# MCU.net
KiCad netlist of a schematic drawn in Altium Designer
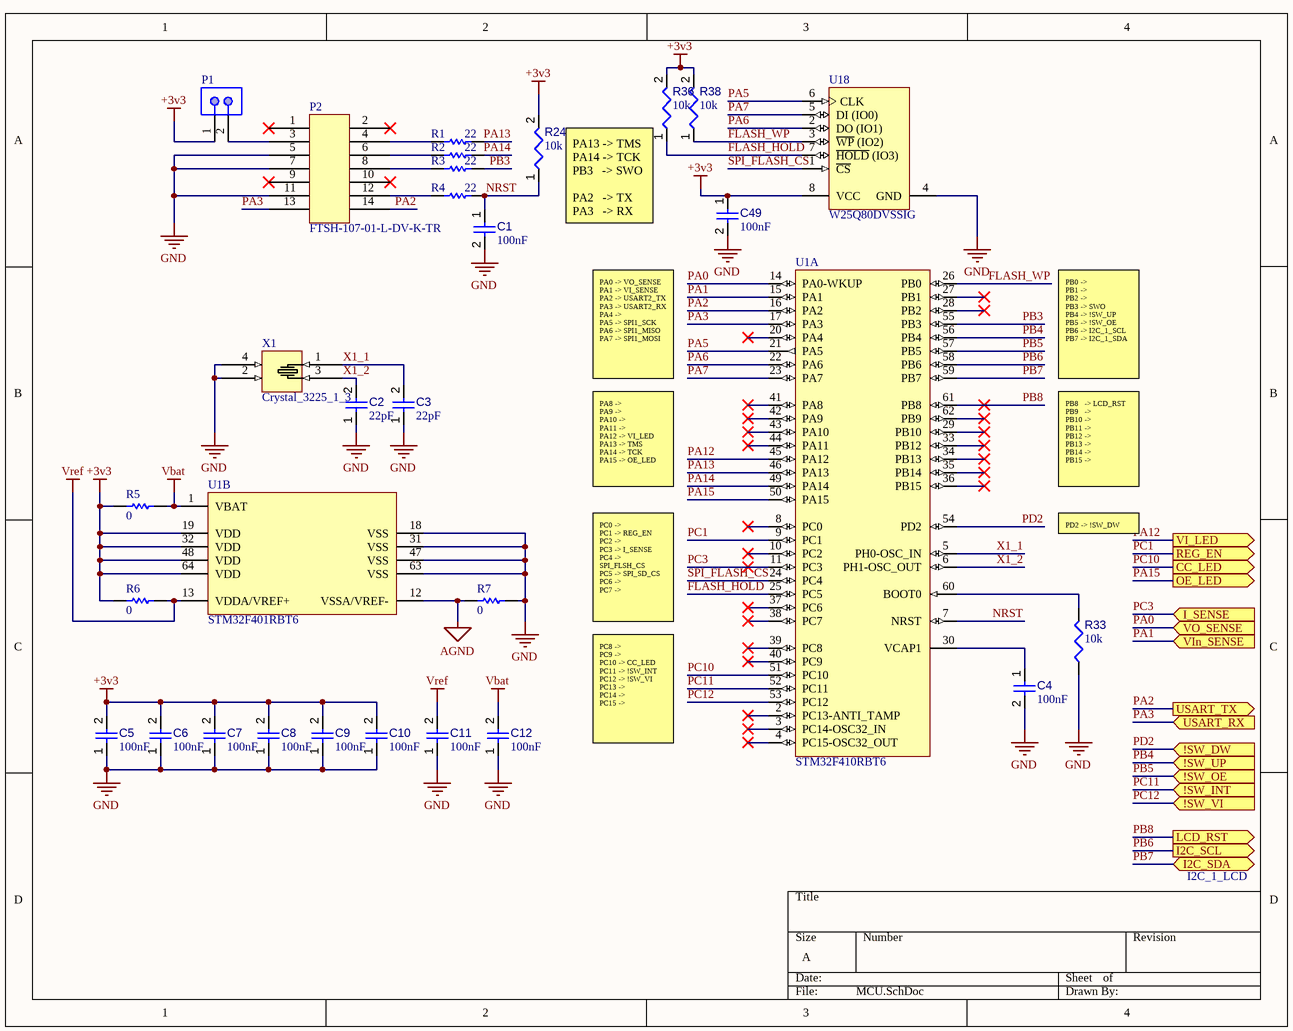
[diagram p0: MCU.SchDoc]

(export (version "E")
  (design (tool "Eeschema 10.0.6"))
  (components
    (comp (ref "C1")
      (value "100nF")
      (footprint "CAPC2013X95X50ML10T25")
      (description "Chip Capacitor, 100 nF, +/- 10%, 50 V, 0805 (2012 Metric)")
      (fields (field (name "TOLERANCE") "10%") (field (name "Comment") "Capacitor 100 nF +/-10% 50 V 0805"))
      (libsource (lib "Aditya Sehgal") (part "CAP-NP-2"))
    )
    (comp (ref "C2")
      (value "22pF")
      (footprint "CAPC2013X95X50ML10T25")
      (description "Chip Capacitor, 100 nF, +/- 10%, 50 V, 0805 (2012 Metric)")
      (fields (field (name "TOLERANCE") "10%") (field (name "Comment") "Capacitor 100 nF +/-10% 50 V 0805"))
      (libsource (lib "Aditya Sehgal") (part "CAP-NP-2"))
    )
    (comp (ref "C3")
      (value "22pF")
      (footprint "CAPC2013X95X50ML10T25")
      (description "Chip Capacitor, 100 nF, +/- 10%, 50 V, 0805 (2012 Metric)")
      (fields (field (name "TOLERANCE") "10%") (field (name "Comment") "Capacitor 100 nF +/-10% 50 V 0805"))
      (libsource (lib "Aditya Sehgal") (part "CAP-NP-2"))
    )
    (comp (ref "C4")
      (value "100nF")
      (footprint "CAPC2013X95X50ML10T25")
      (description "Chip Capacitor, 100 nF, +/- 10%, 50 V, 0805 (2012 Metric)")
      (fields (field (name "TOLERANCE") "10%") (field (name "Comment") "Capacitor 100 nF +/-10% 50 V 0805"))
      (libsource (lib "Aditya Sehgal") (part "CAP-NP-2"))
    )
    (comp (ref "C5")
      (value "100nF")
      (footprint "CAPC2013X95X50ML10T25")
      (description "Chip Capacitor, 100 nF, +/- 10%, 50 V, 0805 (2012 Metric)")
      (fields (field (name "TOLERANCE") "10%") (field (name "Comment") "Capacitor 100 nF +/-10% 50 V 0805"))
      (libsource (lib "Aditya Sehgal") (part "CAP-NP-2"))
    )
    (comp (ref "C6")
      (value "100nF")
      (footprint "CAPC2013X95X50ML10T25")
      (description "Chip Capacitor, 100 nF, +/- 10%, 50 V, 0805 (2012 Metric)")
      (fields (field (name "TOLERANCE") "10%") (field (name "Comment") "Capacitor 100 nF +/-10% 50 V 0805"))
      (libsource (lib "Aditya Sehgal") (part "CAP-NP-2"))
    )
    (comp (ref "C7")
      (value "100nF")
      (footprint "CAPC2013X95X50ML10T25")
      (description "Chip Capacitor, 100 nF, +/- 10%, 50 V, 0805 (2012 Metric)")
      (fields (field (name "TOLERANCE") "10%") (field (name "Comment") "Capacitor 100 nF +/-10% 50 V 0805"))
      (libsource (lib "Aditya Sehgal") (part "CAP-NP-2"))
    )
    (comp (ref "C8")
      (value "100nF")
      (footprint "CAPC2013X95X50ML10T25")
      (description "Chip Capacitor, 100 nF, +/- 10%, 50 V, 0805 (2012 Metric)")
      (fields (field (name "TOLERANCE") "10%") (field (name "Comment") "Capacitor 100 nF +/-10% 50 V 0805"))
      (libsource (lib "Aditya Sehgal") (part "CAP-NP-2"))
    )
    (comp (ref "C9")
      (value "100nF")
      (footprint "CAPC2013X95X50ML10T25")
      (description "Chip Capacitor, 100 nF, +/- 10%, 50 V, 0805 (2012 Metric)")
      (fields (field (name "TOLERANCE") "10%") (field (name "Comment") "Capacitor 100 nF +/-10% 50 V 0805"))
      (libsource (lib "Aditya Sehgal") (part "CAP-NP-2"))
    )
    (comp (ref "C10")
      (value "100nF")
      (footprint "CAPC2013X95X50ML10T25")
      (description "Chip Capacitor, 100 nF, +/- 10%, 50 V, 0805 (2012 Metric)")
      (fields (field (name "TOLERANCE") "10%") (field (name "Comment") "Capacitor 100 nF +/-10% 50 V 0805"))
      (libsource (lib "Aditya Sehgal") (part "CAP-NP-2"))
    )
    (comp (ref "C11")
      (value "100nF")
      (footprint "CAPC2013X95X50ML10T25")
      (description "Chip Capacitor, 100 nF, +/- 10%, 50 V, 0805 (2012 Metric)")
      (fields (field (name "TOLERANCE") "10%") (field (name "Comment") "Capacitor 100 nF +/-10% 50 V 0805"))
      (libsource (lib "Aditya Sehgal") (part "CAP-NP-2"))
    )
    (comp (ref "C12")
      (value "100nF")
      (footprint "CAPC2013X95X50ML10T25")
      (description "Chip Capacitor, 100 nF, +/- 10%, 50 V, 0805 (2012 Metric)")
      (fields (field (name "TOLERANCE") "10%") (field (name "Comment") "Capacitor 100 nF +/-10% 50 V 0805"))
      (libsource (lib "Aditya Sehgal") (part "CAP-NP-2"))
    )
    (comp (ref "C49")
      (value "100nF")
      (footprint "CAPC2013X95X50LL10T25")
      (description "Chip Capacitor, 100 nF, +/- 10%, 50 V, 0805 (2012 Metric)")
      (fields (field (name "TOLERANCE") "10%") (field (name "Comment") "Capacitor 100 nF +/-10% 50 V 0805"))
      (libsource (lib "Knightscope, Inc") (part "CAP-NP-2"))
    )
    (comp (ref "P1")
      (value "GRPB021VWVN-RC")
      (footprint "SLIN-GRPB021VWVN-RC_V")
      (fields (field (name "MANUFACTURER") "Sullins"))
      (libsource (lib "Altium Content Vault") (part "CN-1P-M-R2"))
    )
    (comp (ref "P2")
      (value "FTSH-107-01-L-DV-K-TR")
      (footprint "FTSH-107-01-L-DV-K-TR-Footprint-1")
      (description "Conn Unshrouded Header HDR 14 POS 1.27mm Solder ST SMD T/R")
      (libsource (lib "University of California Santa Cruz") (part "FTSH-107-01-L-DV-K-TR"))
    )
    (comp (ref "R1")
      (value "22")
      (footprint "RESC2013X50X35ML15T15")
      (description "Chip Resistor, 0 Ohm, +/- 1%, 125 mW, -55 to 155 degC, 0805 (2012 Metric)")
      (fields (field (name "TOLERANCE") "1%") (field (name "POWER") "125mW"))
      (libsource (lib "Aditya Sehgal") (part "RES-2"))
    )
    (comp (ref "R2")
      (value "22")
      (footprint "RESC2013X50X35ML15T15")
      (description "Chip Resistor, 0 Ohm, +/- 1%, 125 mW, -55 to 155 degC, 0805 (2012 Metric)")
      (fields (field (name "TOLERANCE") "1%") (field (name "POWER") "125mW"))
      (libsource (lib "Aditya Sehgal") (part "RES-2"))
    )
    (comp (ref "R3")
      (value "22")
      (footprint "RESC2013X50X35ML15T15")
      (description "Chip Resistor, 0 Ohm, +/- 1%, 125 mW, -55 to 155 degC, 0805 (2012 Metric)")
      (fields (field (name "TOLERANCE") "1%") (field (name "POWER") "125mW"))
      (libsource (lib "Aditya Sehgal") (part "RES-2"))
    )
    (comp (ref "R4")
      (value "22")
      (footprint "RESC2013X50X35ML15T15")
      (description "Chip Resistor, 0 Ohm, +/- 1%, 125 mW, -55 to 155 degC, 0805 (2012 Metric)")
      (fields (field (name "TOLERANCE") "1%") (field (name "POWER") "125mW"))
      (libsource (lib "Aditya Sehgal") (part "RES-2"))
    )
    (comp (ref "R5")
      (value "0")
      (footprint "RESC2013X50X35ML15T15")
      (description "Chip Resistor, 0 Ohm, +/- 1%, 125 mW, -55 to 155 degC, 0805 (2012 Metric)")
      (fields (field (name "TOLERANCE") "1%") (field (name "POWER") "125mW"))
      (libsource (lib "Aditya Sehgal") (part "RES-2"))
    )
    (comp (ref "R6")
      (value "0")
      (footprint "RESC2013X50X35ML15T15")
      (description "Chip Resistor, 0 Ohm, +/- 1%, 125 mW, -55 to 155 degC, 0805 (2012 Metric)")
      (fields (field (name "TOLERANCE") "1%") (field (name "POWER") "125mW"))
      (libsource (lib "Aditya Sehgal") (part "RES-2"))
    )
    (comp (ref "R7")
      (value "0")
      (footprint "RESC2013X50X35ML15T15")
      (description "Chip Resistor, 0 Ohm, +/- 1%, 125 mW, -55 to 155 degC, 0805 (2012 Metric)")
      (fields (field (name "TOLERANCE") "1%") (field (name "POWER") "125mW"))
      (libsource (lib "Aditya Sehgal") (part "RES-2"))
    )
    (comp (ref "R24")
      (value "10k")
      (footprint "RESC2013X50X35ML15T15")
      (description "Chip Resistor, 10 KOhm, +/- 1%, 125 mW, -55 to 155 degC, 0805 (2012 Metric)")
      (fields (field (name "TOLERANCE") "1%") (field (name "POWER") "125mW"))
      (libsource (lib "Knightscope, Inc") (part "RES-2"))
    )
    (comp (ref "R33")
      (value "10k")
      (footprint "RESC0805(2012)_L")
      (description "Chip Resistor, 470 Ohms, +/-5%, 125 mW, -55 to 155 degC, 0805")
      (fields (field (name "POWER") "125mW") (field (name "TOLERANCE") "5%"))
      (libsource (lib "University of California Santa Cruz") (part "RES-2"))
    )
    (comp (ref "R36")
      (value "10k")
      (footprint "RESC2013X50X35ML15T15")
      (description "Chip Resistor, 10 KOhm, +/- 1%, 125 mW, -55 to 155 degC, 0805 (2012 Metric)")
      (fields (field (name "TOLERANCE") "1%") (field (name "POWER") "125mW"))
      (libsource (lib "Knightscope, Inc") (part "RES-2"))
    )
    (comp (ref "R38")
      (value "10k")
      (footprint "RESC2013X50X35ML15T15")
      (description "Chip Resistor, 10 KOhm, +/- 1%, 125 mW, -55 to 155 degC, 0805 (2012 Metric)")
      (fields (field (name "TOLERANCE") "1%") (field (name "POWER") "125mW"))
      (libsource (lib "Knightscope, Inc") (part "RES-2"))
    )
    (comp (ref "U1")
      (value "STM32F410RBT6")
      (footprint "STM-LQFP64_N")
      (fields (field (name "MANUFACTURER") "STMicroelectronics") (field (name "PARTNUMBER") "STM32F401RBT6"))
      (libsource (lib "Altium Content Vault") (part "MC-ARM-STM32F401-SQ64"))
    )
    (comp (ref "U18")
      (value "W25Q80DVSSIG")
      (footprint "WINB-SOIC-8_L")
      (fields (field (name "MANUFACTURER") "WinbondElectronics"))
      (libsource (lib "Altium Content Vault") (part "WINB-W25Q80DV-8"))
    )
    (comp (ref "X1")
      (value "Crystal_3225_1_3")
      (footprint "Crystal_3225_1_3-Footprint-1")
      (description "3225 crystal")
      (libsource (lib "Aditya Sehgal") (part "Crystal_4pin_1_3"))
    )
  )
  (nets
    (net (code "1") (name "+3v3") (class "Default")
      (node (ref "C10") (pin "2") (pinfunction "2_2") (pintype "passive"))
      (node (ref "C49") (pin "1") (pinfunction "1_1") (pintype "passive"))
      (node (ref "C5") (pin "2") (pinfunction "2_2") (pintype "passive"))
      (node (ref "C6") (pin "2") (pinfunction "2_2") (pintype "passive"))
      (node (ref "C7") (pin "2") (pinfunction "2_2") (pintype "passive"))
      (node (ref "C8") (pin "2") (pinfunction "2_2") (pintype "passive"))
      (node (ref "C9") (pin "2") (pinfunction "2_2") (pintype "passive"))
      (node (ref "P1") (pin "1") (pinfunction "1_1") (pintype "passive"))
      (node (ref "R24") (pin "2") (pinfunction "2_2") (pintype "passive"))
      (node (ref "R36") (pin "2") (pinfunction "2_2") (pintype "passive"))
      (node (ref "R38") (pin "2") (pinfunction "2_2") (pintype "passive"))
      (node (ref "R5") (pin "1") (pinfunction "1_1") (pintype "passive"))
      (node (ref "R6") (pin "1") (pinfunction "1_1") (pintype "passive"))
      (node (ref "U1") (pin "19") (pinfunction "VDD_19") (pintype "power_in"))
      (node (ref "U1") (pin "32") (pinfunction "VDD_32") (pintype "power_in"))
      (node (ref "U1") (pin "48") (pinfunction "VDD_48") (pintype "power_in"))
      (node (ref "U1") (pin "64") (pinfunction "VDD_64") (pintype "power_in"))
      (node (ref "U18") (pin "8") (pinfunction "VCC_8") (pintype "power_in"))
    )
    (net (code "2") (name "/FLASH_HOLD") (class "Default")
      (node (ref "R36") (pin "1") (pinfunction "1_1") (pintype "passive"))
      (node (ref "U1") (pin "25") (pinfunction "PC5_25") (pintype "bidirectional"))
      (node (ref "U18") (pin "7") (pinfunction "~{HOLD}_(IO3)_7") (pintype "bidirectional"))
    )
    (net (code "3") (name "/FLASH_WP") (class "Default")
      (node (ref "R38") (pin "1") (pinfunction "1_1") (pintype "passive"))
      (node (ref "U1") (pin "26") (pinfunction "PB0_26") (pintype "bidirectional"))
      (node (ref "U18") (pin "3") (pinfunction "~{WP}_(IO2)_3") (pintype "bidirectional"))
    )
    (net (code "4") (name "/NRST") (class "Default")
      (node (ref "C1") (pin "1") (pinfunction "1_1") (pintype "passive"))
      (node (ref "R24") (pin "1") (pinfunction "1_1") (pintype "passive"))
      (node (ref "R4") (pin "2") (pinfunction "2_2") (pintype "passive"))
      (node (ref "U1") (pin "7") (pinfunction "NRST_7") (pintype "bidirectional"))
    )
    (net (code "5") (name "/PA0") (class "Default")
      (node (ref "U1") (pin "14") (pinfunction "PA0-WKUP_14") (pintype "bidirectional"))
    )
    (net (code "6") (name "/PA1") (class "Default")
      (node (ref "U1") (pin "15") (pinfunction "PA1_15") (pintype "bidirectional"))
    )
    (net (code "7") (name "/PA2") (class "Default")
      (node (ref "P2") (pin "14") (pinfunction "14_14") (pintype "passive"))
      (node (ref "U1") (pin "16") (pinfunction "PA2_16") (pintype "bidirectional"))
    )
    (net (code "8") (name "/PA3") (class "Default")
      (node (ref "P2") (pin "13") (pinfunction "13_13") (pintype "passive"))
      (node (ref "U1") (pin "17") (pinfunction "PA3_17") (pintype "bidirectional"))
    )
    (net (code "9") (name "/PA5") (class "Default")
      (node (ref "U1") (pin "21") (pinfunction "PA5_21") (pintype "bidirectional"))
      (node (ref "U18") (pin "6") (pinfunction "CLK_6") (pintype "input"))
    )
    (net (code "10") (name "/PA6") (class "Default")
      (node (ref "U1") (pin "22") (pinfunction "PA6_22") (pintype "bidirectional"))
      (node (ref "U18") (pin "2") (pinfunction "DO_(IO1)_2") (pintype "bidirectional"))
    )
    (net (code "11") (name "/PA7") (class "Default")
      (node (ref "U1") (pin "23") (pinfunction "PA7_23") (pintype "bidirectional"))
      (node (ref "U18") (pin "5") (pinfunction "DI_(IO0)_5") (pintype "bidirectional"))
    )
    (net (code "12") (name "/PA12") (class "Default")
      (node (ref "U1") (pin "45") (pinfunction "PA12_45") (pintype "bidirectional"))
    )
    (net (code "13") (name "/PA13") (class "Default")
      (node (ref "R1") (pin "2") (pinfunction "2_2") (pintype "passive"))
      (node (ref "U1") (pin "46") (pinfunction "PA13_46") (pintype "bidirectional"))
    )
    (net (code "14") (name "/PA14") (class "Default")
      (node (ref "R2") (pin "2") (pinfunction "2_2") (pintype "passive"))
      (node (ref "U1") (pin "49") (pinfunction "PA14_49") (pintype "bidirectional"))
    )
    (net (code "15") (name "/PA15") (class "Default")
      (node (ref "U1") (pin "50") (pinfunction "PA15_50") (pintype "bidirectional"))
    )
    (net (code "16") (name "/PB3") (class "Default")
      (node (ref "R3") (pin "2") (pinfunction "2_2") (pintype "passive"))
      (node (ref "U1") (pin "55") (pinfunction "PB3_55") (pintype "bidirectional"))
    )
    (net (code "17") (name "/PB4") (class "Default")
      (node (ref "U1") (pin "56") (pinfunction "PB4_56") (pintype "bidirectional"))
    )
    (net (code "18") (name "/PB5") (class "Default")
      (node (ref "U1") (pin "57") (pinfunction "PB5_57") (pintype "bidirectional"))
    )
    (net (code "19") (name "/PB6") (class "Default")
      (node (ref "U1") (pin "58") (pinfunction "PB6_58") (pintype "bidirectional"))
    )
    (net (code "20") (name "/PB7") (class "Default")
      (node (ref "U1") (pin "59") (pinfunction "PB7_59") (pintype "bidirectional"))
    )
    (net (code "21") (name "/PB8") (class "Default")
      (node (ref "U1") (pin "61") (pinfunction "PB8_61") (pintype "bidirectional"))
    )
    (net (code "22") (name "/PC1") (class "Default")
      (node (ref "U1") (pin "9") (pinfunction "PC1_9") (pintype "bidirectional"))
    )
    (net (code "23") (name "/PC3") (class "Default")
      (node (ref "U1") (pin "11") (pinfunction "PC3_11") (pintype "bidirectional"))
    )
    (net (code "24") (name "/PC10") (class "Default")
      (node (ref "U1") (pin "51") (pinfunction "PC10_51") (pintype "bidirectional"))
    )
    (net (code "25") (name "/PC11") (class "Default")
      (node (ref "U1") (pin "52") (pinfunction "PC11_52") (pintype "bidirectional"))
    )
    (net (code "26") (name "/PC12") (class "Default")
      (node (ref "U1") (pin "53") (pinfunction "PC12_53") (pintype "bidirectional"))
    )
    (net (code "27") (name "/PD2") (class "Default")
      (node (ref "U1") (pin "54") (pinfunction "PD2_54") (pintype "bidirectional"))
    )
    (net (code "28") (name "/SPI_FLASH_CS") (class "Default")
      (node (ref "U1") (pin "24") (pinfunction "PC4_24") (pintype "bidirectional"))
      (node (ref "U18") (pin "1") (pinfunction "~{CS}_1") (pintype "input"))
    )
    (net (code "29") (name "/X1_1") (class "Default")
      (node (ref "C3") (pin "2") (pinfunction "2_2") (pintype "passive"))
      (node (ref "U1") (pin "5") (pinfunction "PH0-OSC_IN_5") (pintype "bidirectional"))
      (node (ref "X1") (pin "1") (pinfunction "X1_1") (pintype "input"))
    )
    (net (code "30") (name "/X1_2") (class "Default")
      (node (ref "C2") (pin "2") (pinfunction "2_2") (pintype "passive"))
      (node (ref "U1") (pin "6") (pinfunction "PH1-OSC_OUT_6") (pintype "bidirectional"))
      (node (ref "X1") (pin "3") (pinfunction "X2_3") (pintype "input"))
    )
    (net (code "31") (name "AGND") (class "Default")
      (node (ref "R7") (pin "1") (pinfunction "1_1") (pintype "passive"))
      (node (ref "U1") (pin "12") (pinfunction "VSSA/VREF-_12") (pintype "power_in"))
    )
    (net (code "32") (name "GND") (class "Default")
      (node (ref "C1") (pin "2") (pinfunction "2_2") (pintype "passive"))
      (node (ref "C10") (pin "1") (pinfunction "1_1") (pintype "passive"))
      (node (ref "C11") (pin "1") (pinfunction "1_1") (pintype "passive"))
      (node (ref "C12") (pin "1") (pinfunction "1_1") (pintype "passive"))
      (node (ref "C2") (pin "1") (pinfunction "1_1") (pintype "passive"))
      (node (ref "C3") (pin "1") (pinfunction "1_1") (pintype "passive"))
      (node (ref "C4") (pin "2") (pinfunction "2_2") (pintype "passive"))
      (node (ref "C49") (pin "2") (pinfunction "2_2") (pintype "passive"))
      (node (ref "C5") (pin "1") (pinfunction "1_1") (pintype "passive"))
      (node (ref "C6") (pin "1") (pinfunction "1_1") (pintype "passive"))
      (node (ref "C7") (pin "1") (pinfunction "1_1") (pintype "passive"))
      (node (ref "C8") (pin "1") (pinfunction "1_1") (pintype "passive"))
      (node (ref "C9") (pin "1") (pinfunction "1_1") (pintype "passive"))
      (node (ref "P2") (pin "11") (pinfunction "11_11") (pintype "passive"))
      (node (ref "P2") (pin "5") (pinfunction "5_5") (pintype "passive"))
      (node (ref "P2") (pin "7") (pinfunction "7_7") (pintype "passive"))
      (node (ref "R33") (pin "1") (pinfunction "1_1") (pintype "passive"))
      (node (ref "R7") (pin "2") (pinfunction "2_2") (pintype "passive"))
      (node (ref "U1") (pin "18") (pinfunction "VSS_18") (pintype "power_in"))
      (node (ref "U1") (pin "31") (pinfunction "VSS_31") (pintype "power_in"))
      (node (ref "U1") (pin "47") (pinfunction "VSS_47") (pintype "power_in"))
      (node (ref "U1") (pin "63") (pinfunction "VSS_63") (pintype "power_in"))
      (node (ref "U18") (pin "4") (pinfunction "GND_4") (pintype "power_in"))
      (node (ref "X1") (pin "2") (pinfunction "GND_2") (pintype "input"))
      (node (ref "X1") (pin "4") (pinfunction "GND_4") (pintype "input"))
    )
    (net (code "33") (name "Net-(P1-Pad2)") (class "Default")
      (node (ref "P1") (pin "2") (pinfunction "2_2") (pintype "passive"))
      (node (ref "P2") (pin "3") (pinfunction "3_3") (pintype "passive"))
    )
    (net (code "34") (name "Net-(P2-Pad4)") (class "Default")
      (node (ref "P2") (pin "4") (pinfunction "4_4") (pintype "passive"))
      (node (ref "R1") (pin "1") (pinfunction "1_1") (pintype "passive"))
    )
    (net (code "35") (name "Net-(P2-Pad6)") (class "Default")
      (node (ref "P2") (pin "6") (pinfunction "6_6") (pintype "passive"))
      (node (ref "R2") (pin "1") (pinfunction "1_1") (pintype "passive"))
    )
    (net (code "36") (name "Net-(P2-Pad8)") (class "Default")
      (node (ref "P2") (pin "8") (pinfunction "8_8") (pintype "passive"))
      (node (ref "R3") (pin "1") (pinfunction "1_1") (pintype "passive"))
    )
    (net (code "37") (name "Net-(P2-Pad12)") (class "Default")
      (node (ref "P2") (pin "12") (pinfunction "12_12") (pintype "passive"))
      (node (ref "R4") (pin "1") (pinfunction "1_1") (pintype "passive"))
    )
    (net (code "38") (name "Net-(U1A-BOOT0)") (class "Default")
      (node (ref "R33") (pin "2") (pinfunction "2_2") (pintype "passive"))
      (node (ref "U1") (pin "60") (pinfunction "BOOT0_60") (pintype "input"))
    )
    (net (code "39") (name "Net-(U1A-VCAP1)") (class "Default")
      (node (ref "C4") (pin "1") (pinfunction "1_1") (pintype "passive"))
      (node (ref "U1") (pin "30") (pinfunction "VCAP1_30") (pintype "power_in"))
    )
    (net (code "40") (name "Vbat") (class "Default")
      (node (ref "C12") (pin "2") (pinfunction "2_2") (pintype "passive"))
      (node (ref "R5") (pin "2") (pinfunction "2_2") (pintype "passive"))
      (node (ref "U1") (pin "1") (pinfunction "VBAT_1") (pintype "power_in"))
    )
    (net (code "41") (name "Vref") (class "Default")
      (node (ref "C11") (pin "2") (pinfunction "2_2") (pintype "passive"))
      (node (ref "R6") (pin "2") (pinfunction "2_2") (pintype "passive"))
      (node (ref "U1") (pin "13") (pinfunction "VDDA/VREF+_13") (pintype "power_in"))
    )
    (net (code "42") (name "unconnected-(P2-Pad1)") (class "Default")
      (node (ref "P2") (pin "1") (pinfunction "1_1") (pintype "passive+no_connect"))
    )
    (net (code "43") (name "unconnected-(P2-Pad2)") (class "Default")
      (node (ref "P2") (pin "2") (pinfunction "2_2") (pintype "passive+no_connect"))
    )
    (net (code "44") (name "unconnected-(P2-Pad9)") (class "Default")
      (node (ref "P2") (pin "9") (pinfunction "9_9") (pintype "passive+no_connect"))
    )
    (net (code "45") (name "unconnected-(P2-Pad10)") (class "Default")
      (node (ref "P2") (pin "10") (pinfunction "10_10") (pintype "passive+no_connect"))
    )
    (net (code "46") (name "unconnected-(U1A-PA4-Pad20)") (class "Default")
      (node (ref "U1") (pin "20") (pinfunction "PA4_20") (pintype "bidirectional+no_connect"))
    )
    (net (code "47") (name "unconnected-(U1A-PA8-Pad41)") (class "Default")
      (node (ref "U1") (pin "41") (pinfunction "PA8_41") (pintype "bidirectional+no_connect"))
    )
    (net (code "48") (name "unconnected-(U1A-PA9-Pad42)") (class "Default")
      (node (ref "U1") (pin "42") (pinfunction "PA9_42") (pintype "bidirectional+no_connect"))
    )
    (net (code "49") (name "unconnected-(U1A-PA10-Pad43)") (class "Default")
      (node (ref "U1") (pin "43") (pinfunction "PA10_43") (pintype "bidirectional+no_connect"))
    )
    (net (code "50") (name "unconnected-(U1A-PA11-Pad44)") (class "Default")
      (node (ref "U1") (pin "44") (pinfunction "PA11_44") (pintype "bidirectional+no_connect"))
    )
    (net (code "51") (name "unconnected-(U1A-PB1-Pad27)") (class "Default")
      (node (ref "U1") (pin "27") (pinfunction "PB1_27") (pintype "bidirectional+no_connect"))
    )
    (net (code "52") (name "unconnected-(U1A-PB2-Pad28)") (class "Default")
      (node (ref "U1") (pin "28") (pinfunction "PB2_28") (pintype "bidirectional+no_connect"))
    )
    (net (code "53") (name "unconnected-(U1A-PB9-Pad62)") (class "Default")
      (node (ref "U1") (pin "62") (pinfunction "PB9_62") (pintype "bidirectional+no_connect"))
    )
    (net (code "54") (name "unconnected-(U1A-PB10-Pad29)") (class "Default")
      (node (ref "U1") (pin "29") (pinfunction "PB10_29") (pintype "bidirectional+no_connect"))
    )
    (net (code "55") (name "unconnected-(U1A-PB12-Pad33)") (class "Default")
      (node (ref "U1") (pin "33") (pinfunction "PB12_33") (pintype "bidirectional+no_connect"))
    )
    (net (code "56") (name "unconnected-(U1A-PB13-Pad34)") (class "Default")
      (node (ref "U1") (pin "34") (pinfunction "PB13_34") (pintype "bidirectional+no_connect"))
    )
    (net (code "57") (name "unconnected-(U1A-PB14-Pad35)") (class "Default")
      (node (ref "U1") (pin "35") (pinfunction "PB14_35") (pintype "bidirectional+no_connect"))
    )
    (net (code "58") (name "unconnected-(U1A-PB15-Pad36)") (class "Default")
      (node (ref "U1") (pin "36") (pinfunction "PB15_36") (pintype "bidirectional+no_connect"))
    )
    (net (code "59") (name "unconnected-(U1A-PC0-Pad8)") (class "Default")
      (node (ref "U1") (pin "8") (pinfunction "PC0_8") (pintype "bidirectional+no_connect"))
    )
    (net (code "60") (name "unconnected-(U1A-PC2-Pad10)") (class "Default")
      (node (ref "U1") (pin "10") (pinfunction "PC2_10") (pintype "bidirectional+no_connect"))
    )
    (net (code "61") (name "unconnected-(U1A-PC6-Pad37)") (class "Default")
      (node (ref "U1") (pin "37") (pinfunction "PC6_37") (pintype "bidirectional+no_connect"))
    )
    (net (code "62") (name "unconnected-(U1A-PC7-Pad38)") (class "Default")
      (node (ref "U1") (pin "38") (pinfunction "PC7_38") (pintype "bidirectional+no_connect"))
    )
    (net (code "63") (name "unconnected-(U1A-PC8-Pad39)") (class "Default")
      (node (ref "U1") (pin "39") (pinfunction "PC8_39") (pintype "bidirectional+no_connect"))
    )
    (net (code "64") (name "unconnected-(U1A-PC9-Pad40)") (class "Default")
      (node (ref "U1") (pin "40") (pinfunction "PC9_40") (pintype "bidirectional+no_connect"))
    )
    (net (code "65") (name "unconnected-(U1A-PC13-ANTI_TAMP-Pad2)") (class "Default")
      (node (ref "U1") (pin "2") (pinfunction "PC13-ANTI_TAMP_2") (pintype "bidirectional+no_connect"))
    )
    (net (code "66") (name "unconnected-(U1A-PC14-OSC32_IN-Pad3)") (class "Default")
      (node (ref "U1") (pin "3") (pinfunction "PC14-OSC32_IN_3") (pintype "bidirectional+no_connect"))
    )
    (net (code "67") (name "unconnected-(U1A-PC15-OSC32_OUT-Pad4)") (class "Default")
      (node (ref "U1") (pin "4") (pinfunction "PC15-OSC32_OUT_4") (pintype "bidirectional+no_connect"))
    )
  )
)
